# Temp_Hum_Sensor_Schematic_Rev1.net
KiCad netlist of a schematic drawn in EAGLE
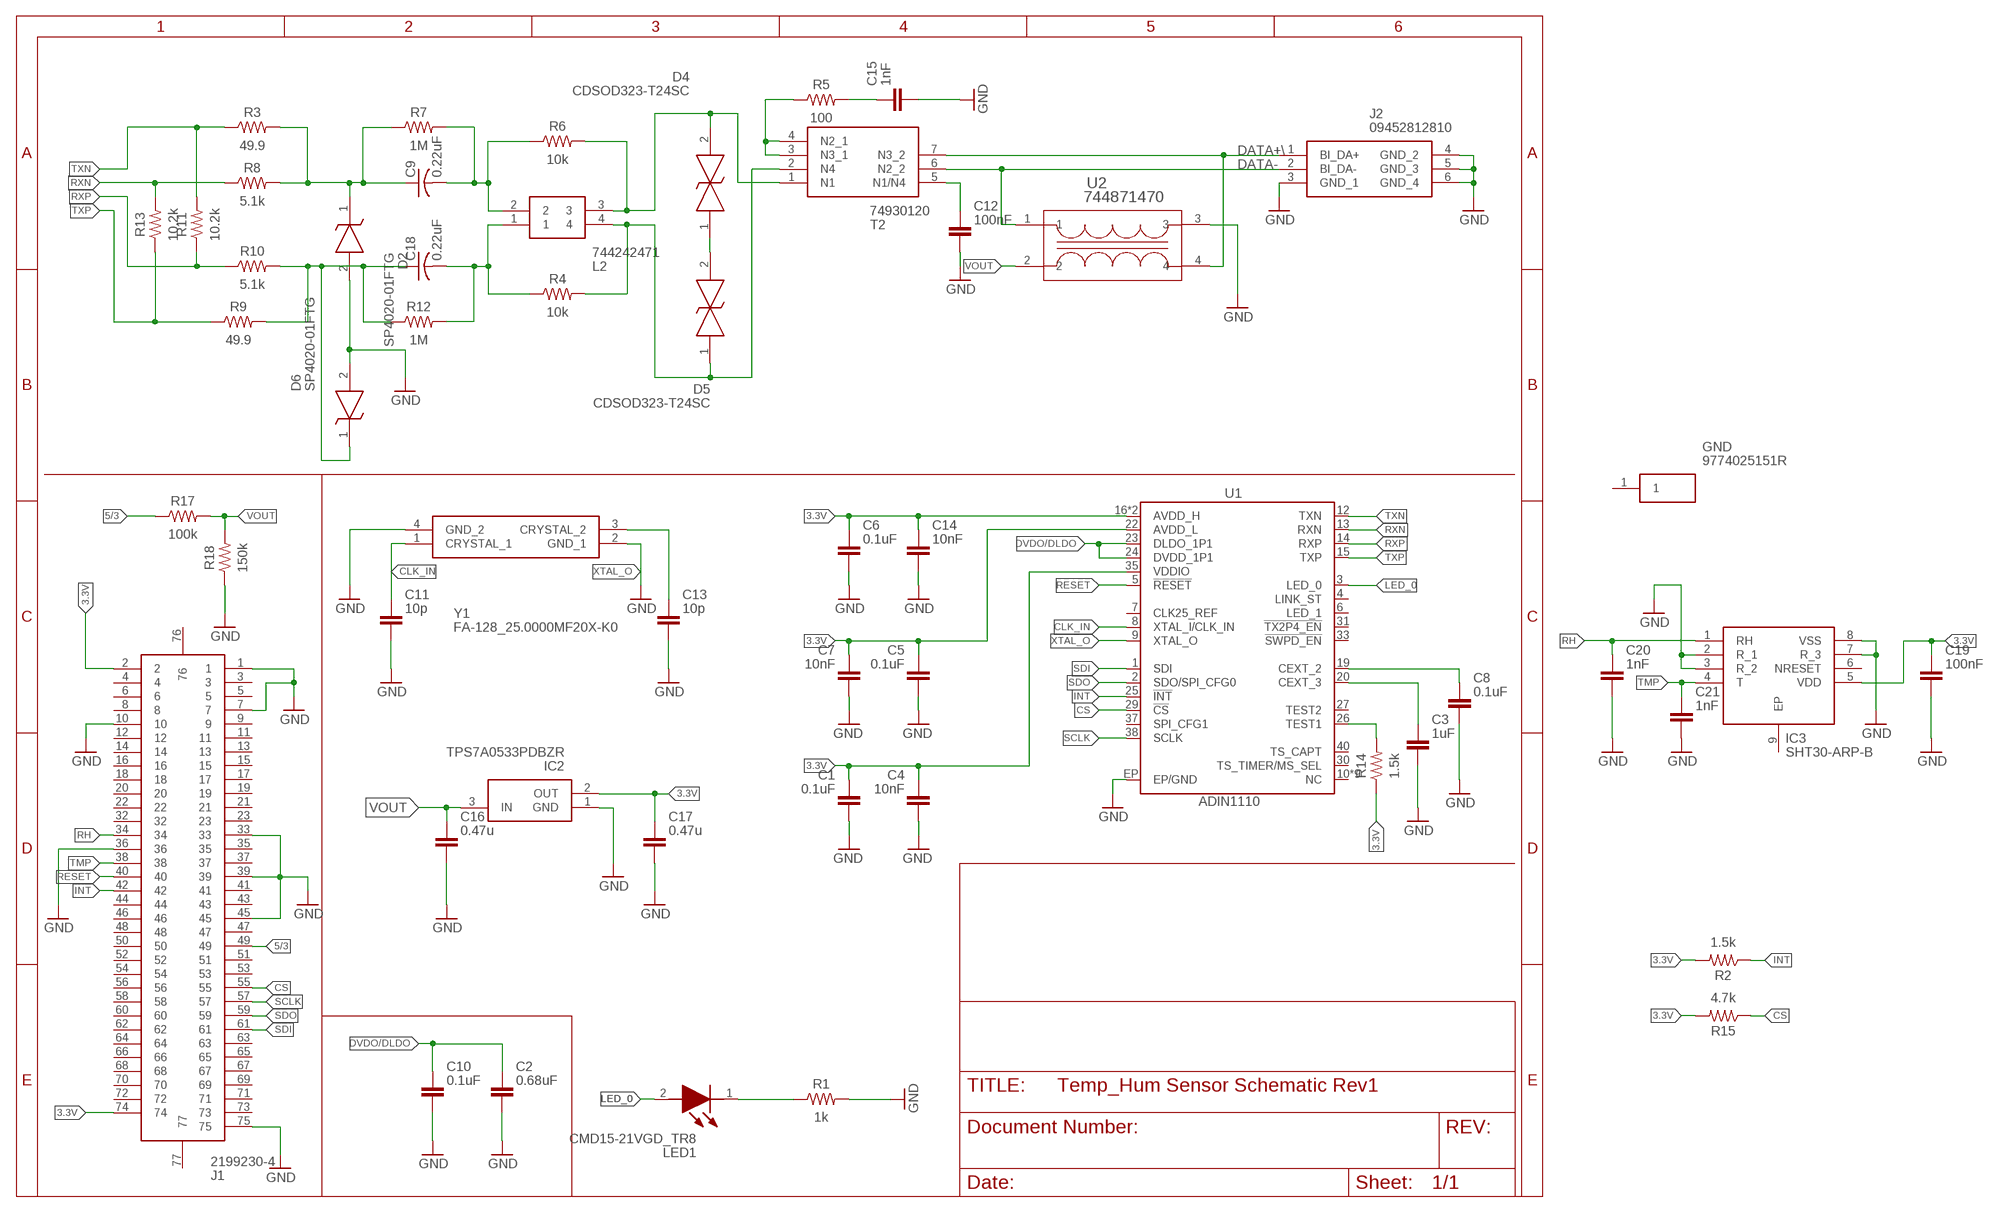
[diagram p0: schematic, sheet 1]

(export (version "E")
  (design (tool "Eeschema 10.0.6"))
  (components
    (comp (ref "C1")
      (value "0.1uF")
      (footprint "eagle-import:CAPC1005X60")
      (libsource (lib "eagle-import") (part "CCHIP-0402(1005-METRIC)_"))
    )
    (comp (ref "C2")
      (value "0.68uF")
      (footprint "eagle-import:CAPC1005X60")
      (libsource (lib "eagle-import") (part "CCHIP-0402(1005-METRIC)_"))
    )
    (comp (ref "C3")
      (value "1uF")
      (footprint "eagle-import:CAPC1005X60")
      (libsource (lib "eagle-import") (part "CCHIP-0402(1005-METRIC)_"))
    )
    (comp (ref "C4")
      (value "10nF")
      (footprint "eagle-import:CAPC1005X60")
      (libsource (lib "eagle-import") (part "CCHIP-0402(1005-METRIC)_"))
    )
    (comp (ref "C5")
      (value "0.1uF")
      (footprint "eagle-import:CAPC1005X60")
      (libsource (lib "eagle-import") (part "CCHIP-0402(1005-METRIC)_"))
    )
    (comp (ref "C6")
      (value "0.1uF")
      (footprint "eagle-import:CAPC1005X60")
      (libsource (lib "eagle-import") (part "CCHIP-0402(1005-METRIC)_"))
    )
    (comp (ref "C7")
      (value "10nF")
      (footprint "eagle-import:CAPC1005X60")
      (libsource (lib "eagle-import") (part "CCHIP-0402(1005-METRIC)_"))
    )
    (comp (ref "C8")
      (value "0.1uF")
      (footprint "eagle-import:CAPC1005X60")
      (libsource (lib "eagle-import") (part "CCHIP-0402(1005-METRIC)_"))
    )
    (comp (ref "C9")
      (value "0.22uF")
      (footprint "eagle-import:CAPC3216X135")
      (libsource (lib "eagle-import") (part "C-USCHIP-1206(3216-METRIC)_"))
    )
    (comp (ref "C10")
      (value "0.1uF")
      (footprint "eagle-import:CAPC1005X60")
      (libsource (lib "eagle-import") (part "CCHIP-0402(1005-METRIC)_"))
    )
    (comp (ref "C11")
      (value "10p")
      (footprint "eagle-import:CAPC1005X60")
      (libsource (lib "eagle-import") (part "CCHIP-0402(1005-METRIC)_"))
    )
    (comp (ref "C12")
      (value "100nF")
      (footprint "eagle-import:CAPC1005X60")
      (libsource (lib "eagle-import") (part "CCHIP-0402(1005-METRIC)_"))
    )
    (comp (ref "C13")
      (value "10p")
      (footprint "eagle-import:CAPC1005X60")
      (libsource (lib "eagle-import") (part "CCHIP-0402(1005-METRIC)_"))
    )
    (comp (ref "C14")
      (value "10nF")
      (footprint "eagle-import:CAPC1005X60")
      (libsource (lib "eagle-import") (part "CCHIP-0402(1005-METRIC)_"))
    )
    (comp (ref "C15")
      (value "1nF")
      (footprint "eagle-import:CAPC1005X60")
      (libsource (lib "eagle-import") (part "CCHIP-0402(1005-METRIC)_"))
    )
    (comp (ref "C16")
      (value "0.47u")
      (footprint "eagle-import:CAPC1005X60")
      (libsource (lib "eagle-import") (part "CCHIP-0402(1005-METRIC)_"))
    )
    (comp (ref "C17")
      (value "0.47u")
      (footprint "eagle-import:CAPC1005X60")
      (libsource (lib "eagle-import") (part "CCHIP-0402(1005-METRIC)_"))
    )
    (comp (ref "C18")
      (value "0.22uF")
      (footprint "eagle-import:CAPC3216X135")
      (libsource (lib "eagle-import") (part "C-USCHIP-1206(3216-METRIC)_"))
    )
    (comp (ref "C19")
      (value "100nF")
      (footprint "eagle-import:CAPC1005X60")
      (libsource (lib "eagle-import") (part "CCHIP-0402(1005-METRIC)_"))
    )
    (comp (ref "C20")
      (value "1nF")
      (footprint "eagle-import:CAPC1005X60")
      (libsource (lib "eagle-import") (part "CCHIP-0402(1005-METRIC)_"))
    )
    (comp (ref "C21")
      (value "1nF")
      (footprint "eagle-import:CAPC1005X60")
      (libsource (lib "eagle-import") (part "CCHIP-0402(1005-METRIC)_"))
    )
    (comp (ref "D2")
      (value "SP4020-01FTG")
      (footprint "eagle-import:SOD2613X114N")
      (fields (field (name "MOUSER_PART_NUMBER") "576-SP4020-01FTG"))
      (libsource (lib "eagle-import") (part "SP4020-01FTG"))
    )
    (comp (ref "D4")
      (value "CDSOD323-T24SC")
      (footprint "eagle-import:SOD2513X114N")
      (fields (field (name "MOUSER_PART_NUMBER") "652-CDSOD323-T24SC"))
      (libsource (lib "eagle-import") (part "CDSOD323-T24SC"))
    )
    (comp (ref "D5")
      (value "CDSOD323-T24SC")
      (footprint "eagle-import:SOD2513X114N")
      (fields (field (name "MOUSER_PART_NUMBER") "652-CDSOD323-T24SC"))
      (libsource (lib "eagle-import") (part "CDSOD323-T24SC"))
    )
    (comp (ref "D6")
      (value "SP4020-01FTG")
      (footprint "eagle-import:SOD2613X114N")
      (fields (field (name "MOUSER_PART_NUMBER") "576-SP4020-01FTG"))
      (libsource (lib "eagle-import") (part "SP4020-01FTG"))
    )
    (comp (ref "GND")
      (value "9774025151R")
      (footprint "eagle-import:9774025151R")
      (fields (field (name "MOUSER_PART_NUMBER") "710-9774025151R"))
      (libsource (lib "eagle-import") (part "9774025151R"))
    )
    (comp (ref "IC2")
      (value "TPS7A0533PDBZR")
      (footprint "eagle-import:SOT95P237X112-3N")
      (fields (field (name "MOUSER_PART_NUMBER") "595-TPS7A0533PDBZR"))
      (libsource (lib "eagle-import") (part "TPS7A0533PDBZR"))
    )
    (comp (ref "IC3")
      (value "SHT30-ARP-B")
      (footprint "eagle-import:SON50P250X250X100-9N")
      (fields (field (name "MOUSER_PART_NUMBER") "403-SHT30-ARP-B"))
      (libsource (lib "eagle-import") (part "SHT30-ARP-B"))
    )
    (comp (ref "J1")
      (value "2199230-4")
      (footprint "eagle-import:21992304")
      (fields (field (name "MOUSER_PART_NUMBER") "571-2199230-4"))
      (libsource (lib "eagle-import") (part "2199230-4"))
    )
    (comp (ref "J2")
      (value "09452812810")
      (footprint "eagle-import:09452812810")
      (fields (field (name "MOUSER_PART_NUMBER") "617-09452812810"))
      (libsource (lib "eagle-import") (part "09452812810"))
    )
    (comp (ref "L2")
      (value "744242471")
      (footprint "eagle-import:744242471")
      (fields (field (name "MOUSER_PART_NUMBER") "710-744242471"))
      (libsource (lib "eagle-import") (part "744242471"))
    )
    (comp (ref "LED1")
      (value "CMD15-21VGD_TR8")
      (footprint "eagle-import:LEDC3215X130N")
      (fields
        (field (name "ARROW_PART_NUMBER") "CMD15-21VGD/TR8")
        (field (name "MOUSER_PART_NUMBER") "606-CMD15-21VGD/TR8")
      )
      (libsource (lib "eagle-import") (part "CMD15-21VGD_TR8"))
    )
    (comp (ref "R1")
      (value "1k")
      (footprint "eagle-import:RESC1005X40")
      (libsource (lib "eagle-import") (part "R-USCHIP-0402(1005-METRIC)_"))
    )
    (comp (ref "R2")
      (value "1.5k")
      (footprint "eagle-import:RESC1005X40")
      (libsource (lib "eagle-import") (part "R-USCHIP-0402(1005-METRIC)_"))
    )
    (comp (ref "R3")
      (value "49.9")
      (footprint "eagle-import:RESC1005X40")
      (libsource (lib "eagle-import") (part "R-USCHIP-0402(1005-METRIC)_"))
    )
    (comp (ref "R4")
      (value "10k")
      (footprint "eagle-import:RESC1005X40")
      (libsource (lib "eagle-import") (part "R-USCHIP-0402(1005-METRIC)_"))
    )
    (comp (ref "R5")
      (value "100")
      (footprint "eagle-import:RESC1005X40")
      (libsource (lib "eagle-import") (part "R-USCHIP-0402(1005-METRIC)_"))
    )
    (comp (ref "R6")
      (value "10k")
      (footprint "eagle-import:RESC1005X40")
      (libsource (lib "eagle-import") (part "R-USCHIP-0402(1005-METRIC)_"))
    )
    (comp (ref "R7")
      (value "1M")
      (footprint "eagle-import:RESC1005X40")
      (libsource (lib "eagle-import") (part "R-USCHIP-0402(1005-METRIC)_"))
    )
    (comp (ref "R8")
      (value "5.1k")
      (footprint "eagle-import:RESC1005X40")
      (libsource (lib "eagle-import") (part "R-USCHIP-0402(1005-METRIC)_"))
    )
    (comp (ref "R9")
      (value "49.9")
      (footprint "eagle-import:RESC1005X40")
      (libsource (lib "eagle-import") (part "R-USCHIP-0402(1005-METRIC)_"))
    )
    (comp (ref "R10")
      (value "5.1k")
      (footprint "eagle-import:RESC1005X40")
      (libsource (lib "eagle-import") (part "R-USCHIP-0402(1005-METRIC)_"))
    )
    (comp (ref "R11")
      (value "10.2k")
      (footprint "eagle-import:RESC1005X40")
      (libsource (lib "eagle-import") (part "R-USCHIP-0402(1005-METRIC)_"))
    )
    (comp (ref "R12")
      (value "1M")
      (footprint "eagle-import:RESC1005X40")
      (libsource (lib "eagle-import") (part "R-USCHIP-0402(1005-METRIC)_"))
    )
    (comp (ref "R13")
      (value "10.2k")
      (footprint "eagle-import:RESC1005X40")
      (libsource (lib "eagle-import") (part "R-USCHIP-0402(1005-METRIC)_"))
    )
    (comp (ref "R14")
      (value "1.5k")
      (footprint "eagle-import:RESC1005X40")
      (libsource (lib "eagle-import") (part "R-USCHIP-0402(1005-METRIC)_"))
    )
    (comp (ref "R15")
      (value "4.7k")
      (footprint "eagle-import:RESC1005X40")
      (libsource (lib "eagle-import") (part "R-USCHIP-0402(1005-METRIC)_"))
    )
    (comp (ref "R17")
      (value "100k")
      (footprint "eagle-import:RESC1005X40")
      (libsource (lib "eagle-import") (part "R-USCHIP-0402(1005-METRIC)_"))
    )
    (comp (ref "R18")
      (value "150k")
      (footprint "eagle-import:RESC1005X40")
      (libsource (lib "eagle-import") (part "R-USCHIP-0402(1005-METRIC)_"))
    )
    (comp (ref "T2")
      (value "74930120")
      (footprint "eagle-import:74930120")
      (fields (field (name "MOUSER_PART_NUMBER") "710-74930120"))
      (libsource (lib "eagle-import") (part "74930120"))
    )
    (comp (ref "U1")
      (value "ADIN1110")
      (footprint "eagle-import:LFCSP-40")
      (libsource (lib "eagle-import") (part "ADIN1110"))
    )
    (comp (ref "U2")
      (value "744871470")
      (footprint "eagle-import:SMT_871470_WRE")
      (fields (field (name "COPYRIGHT") "Copyright (C) 2023 Ultra Librarian. All rights reserved."))
      (libsource (lib "eagle-import") (part "744871470"))
    )
    (comp (ref "Y1")
      (value "FA-128_25.0000MF20X-K0")
      (footprint "eagle-import:FA128250000MF20XK0")
      (fields
        (field (name "MANUFACTURER_PART_NUMBER") "FA-128 25.0000MF20X-K0")
        (field (name "MOUSER_PART_NUMBER") "732-FA-12825F20X-K0")
      )
      (libsource (lib "eagle-import") (part "FA-128_25.0000MF20X-K0"))
    )
  )
  (nets
    (net (code "1") (name "/DATA+\\") (class "Default")
      (node (ref "J2") (pin "1") (pinfunction "BI_DA+_1") (pintype "bidirectional"))
      (node (ref "T2") (pin "7") (pinfunction "N3_2_7") (pintype "bidirectional"))
      (node (ref "U2") (pin "4") (pinfunction "4_4") (pintype "passive"))
    )
    (net (code "2") (name "/DATA-") (class "Default")
      (node (ref "J2") (pin "2") (pinfunction "BI_DA-_2") (pintype "bidirectional"))
      (node (ref "T2") (pin "6") (pinfunction "N2_2_6") (pintype "bidirectional"))
      (node (ref "U2") (pin "1") (pinfunction "1_1") (pintype "passive"))
    )
    (net (code "3") (name "3.3V") (class "Default")
      (node (ref "C1") (pin "1") (pinfunction "1_1") (pintype "passive"))
      (node (ref "C14") (pin "1") (pinfunction "1_1") (pintype "passive"))
      (node (ref "C17") (pin "1") (pinfunction "1_1") (pintype "passive"))
      (node (ref "C19") (pin "1") (pinfunction "1_1") (pintype "passive"))
      (node (ref "C4") (pin "1") (pinfunction "1_1") (pintype "passive"))
      (node (ref "C5") (pin "1") (pinfunction "1_1") (pintype "passive"))
      (node (ref "C6") (pin "1") (pinfunction "1_1") (pintype "passive"))
      (node (ref "C7") (pin "1") (pinfunction "1_1") (pintype "passive"))
      (node (ref "IC2") (pin "2") (pinfunction "OUT_2") (pintype "output"))
      (node (ref "IC3") (pin "5") (pinfunction "VDD_5") (pintype "bidirectional"))
      (node (ref "J1") (pin "2") (pinfunction "2_2") (pintype "bidirectional"))
      (node (ref "J1") (pin "74") (pinfunction "74_74") (pintype "bidirectional"))
      (node (ref "R14") (pin "1") (pinfunction "1_1") (pintype "passive"))
      (node (ref "R15") (pin "2") (pinfunction "2_2") (pintype "passive"))
      (node (ref "R2") (pin "2") (pinfunction "2_2") (pintype "passive"))
      (node (ref "U1") (pin "16") (pinfunction "AVDD_H_16") (pintype "bidirectional"))
      (node (ref "U1") (pin "17") (pinfunction "AVDD_H_17") (pintype "bidirectional"))
      (node (ref "U1") (pin "22") (pinfunction "AVDD_L_22") (pintype "bidirectional"))
      (node (ref "U1") (pin "35") (pinfunction "VDDIO_35") (pintype "bidirectional"))
    )
    (net (code "4") (name "5{slash}3") (class "Default")
      (node (ref "J1") (pin "49") (pinfunction "49_49") (pintype "bidirectional"))
      (node (ref "R17") (pin "1") (pinfunction "1_1") (pintype "passive"))
    )
    (net (code "5") (name "CLK_IN") (class "Default")
      (node (ref "C11") (pin "1") (pinfunction "1_1") (pintype "passive"))
      (node (ref "U1") (pin "8") (pinfunction "XTAL_I/CLK_IN_8") (pintype "bidirectional"))
      (node (ref "Y1") (pin "1") (pinfunction "CRYSTAL_1_1") (pintype "bidirectional"))
    )
    (net (code "6") (name "CS") (class "Default")
      (node (ref "J1") (pin "55") (pinfunction "55_55") (pintype "bidirectional"))
      (node (ref "R15") (pin "1") (pinfunction "1_1") (pintype "passive"))
      (node (ref "U1") (pin "29") (pinfunction "~{CS}_29") (pintype "bidirectional"))
    )
    (net (code "7") (name "DVDO{slash}DLDO") (class "Default")
      (node (ref "C10") (pin "1") (pinfunction "1_1") (pintype "passive"))
      (node (ref "C2") (pin "1") (pinfunction "1_1") (pintype "passive"))
      (node (ref "U1") (pin "23") (pinfunction "DLDO_1P1_23") (pintype "bidirectional"))
      (node (ref "U1") (pin "24") (pinfunction "DVDD_1P1_24") (pintype "bidirectional"))
    )
    (net (code "8") (name "GND") (class "Default")
      (node (ref "C1") (pin "2") (pinfunction "2_2") (pintype "passive"))
      (node (ref "C10") (pin "2") (pinfunction "2_2") (pintype "passive"))
      (node (ref "C11") (pin "2") (pinfunction "2_2") (pintype "passive"))
      (node (ref "C12") (pin "2") (pinfunction "2_2") (pintype "passive"))
      (node (ref "C13") (pin "2") (pinfunction "2_2") (pintype "passive"))
      (node (ref "C14") (pin "2") (pinfunction "2_2") (pintype "passive"))
      (node (ref "C15") (pin "2") (pinfunction "2_2") (pintype "passive"))
      (node (ref "C16") (pin "2") (pinfunction "2_2") (pintype "passive"))
      (node (ref "C17") (pin "2") (pinfunction "2_2") (pintype "passive"))
      (node (ref "C19") (pin "2") (pinfunction "2_2") (pintype "passive"))
      (node (ref "C2") (pin "2") (pinfunction "2_2") (pintype "passive"))
      (node (ref "C20") (pin "2") (pinfunction "2_2") (pintype "passive"))
      (node (ref "C21") (pin "2") (pinfunction "2_2") (pintype "passive"))
      (node (ref "C3") (pin "2") (pinfunction "2_2") (pintype "passive"))
      (node (ref "C4") (pin "2") (pinfunction "2_2") (pintype "passive"))
      (node (ref "C5") (pin "2") (pinfunction "2_2") (pintype "passive"))
      (node (ref "C6") (pin "2") (pinfunction "2_2") (pintype "passive"))
      (node (ref "C7") (pin "2") (pinfunction "2_2") (pintype "passive"))
      (node (ref "C8") (pin "2") (pinfunction "2_2") (pintype "passive"))
      (node (ref "D2") (pin "2") (pinfunction "A_2") (pintype "bidirectional"))
      (node (ref "D6") (pin "2") (pinfunction "A_2") (pintype "bidirectional"))
      (node (ref "IC2") (pin "1") (pinfunction "GND_1") (pintype "power_in"))
      (node (ref "IC3") (pin "2") (pinfunction "R_1_2") (pintype "bidirectional"))
      (node (ref "IC3") (pin "3") (pinfunction "R_2_3") (pintype "bidirectional"))
      (node (ref "IC3") (pin "7") (pinfunction "R_3_7") (pintype "bidirectional"))
      (node (ref "IC3") (pin "8") (pinfunction "VSS_8") (pintype "bidirectional"))
      (node (ref "J1") (pin "1") (pinfunction "1_1") (pintype "bidirectional"))
      (node (ref "J1") (pin "10") (pinfunction "10_10") (pintype "bidirectional"))
      (node (ref "J1") (pin "33") (pinfunction "33_33") (pintype "bidirectional"))
      (node (ref "J1") (pin "36") (pinfunction "36_36") (pintype "bidirectional"))
      (node (ref "J1") (pin "39") (pinfunction "39_39") (pintype "bidirectional"))
      (node (ref "J1") (pin "45") (pinfunction "45_45") (pintype "bidirectional"))
      (node (ref "J1") (pin "7") (pinfunction "7_7") (pintype "bidirectional"))
      (node (ref "J1") (pin "75") (pinfunction "75_75") (pintype "bidirectional"))
      (node (ref "J2") (pin "3") (pinfunction "GND_1_3") (pintype "bidirectional"))
      (node (ref "J2") (pin "4") (pinfunction "GND_2_4") (pintype "bidirectional"))
      (node (ref "J2") (pin "5") (pinfunction "GND_3_5") (pintype "bidirectional"))
      (node (ref "J2") (pin "6") (pinfunction "GND_4_6") (pintype "bidirectional"))
      (node (ref "R1") (pin "2") (pinfunction "2_2") (pintype "passive"))
      (node (ref "R18") (pin "1") (pinfunction "1_1") (pintype "passive"))
      (node (ref "U1") (pin "EP") (pinfunction "EP/GND_EP") (pintype "bidirectional"))
      (node (ref "U2") (pin "3") (pinfunction "3_3") (pintype "passive"))
      (node (ref "Y1") (pin "2") (pinfunction "GND_1_2") (pintype "bidirectional"))
      (node (ref "Y1") (pin "4") (pinfunction "GND_2_4") (pintype "bidirectional"))
    )
    (net (code "9") (name "INT") (class "Default")
      (node (ref "J1") (pin "42") (pinfunction "42_42") (pintype "bidirectional"))
      (node (ref "R2") (pin "1") (pinfunction "1_1") (pintype "passive"))
      (node (ref "U1") (pin "25") (pinfunction "~{INT}_25") (pintype "bidirectional"))
    )
    (net (code "10") (name "LED_0") (class "Default")
      (node (ref "LED1") (pin "2") (pinfunction "A_2") (pintype "bidirectional"))
      (node (ref "U1") (pin "3") (pinfunction "LED_0_3") (pintype "bidirectional"))
    )
    (net (code "11") (name "Net-(C9-Pad2)") (class "Default")
      (node (ref "C9") (pin "2") (pinfunction "2_2") (pintype "passive"))
      (node (ref "L2") (pin "2") (pinfunction "2_2") (pintype "bidirectional"))
      (node (ref "R6") (pin "1") (pinfunction "1_1") (pintype "passive"))
      (node (ref "R7") (pin "2") (pinfunction "2_2") (pintype "passive"))
    )
    (net (code "12") (name "Net-(C15-Pad1)") (class "Default")
      (node (ref "C15") (pin "1") (pinfunction "1_1") (pintype "passive"))
      (node (ref "R5") (pin "2") (pinfunction "2_2") (pintype "passive"))
    )
    (net (code "13") (name "Net-(C18-Pad2)") (class "Default")
      (node (ref "C18") (pin "2") (pinfunction "2_2") (pintype "passive"))
      (node (ref "L2") (pin "1") (pinfunction "1_1") (pintype "bidirectional"))
      (node (ref "R12") (pin "2") (pinfunction "2_2") (pintype "passive"))
      (node (ref "R4") (pin "1") (pinfunction "1_1") (pintype "passive"))
    )
    (net (code "14") (name "Net-(D2-K)") (class "Default")
      (node (ref "C9") (pin "1") (pinfunction "1_1") (pintype "passive"))
      (node (ref "D2") (pin "1") (pinfunction "K_1") (pintype "bidirectional"))
      (node (ref "R3") (pin "2") (pinfunction "2_2") (pintype "passive"))
      (node (ref "R7") (pin "1") (pinfunction "1_1") (pintype "passive"))
      (node (ref "R8") (pin "2") (pinfunction "2_2") (pintype "passive"))
    )
    (net (code "15") (name "Net-(D4-Pad1)") (class "Default")
      (node (ref "D4") (pin "1") (pinfunction "1_1") (pintype "bidirectional"))
      (node (ref "D5") (pin "2") (pinfunction "2_2") (pintype "bidirectional"))
    )
    (net (code "16") (name "Net-(D6-K)") (class "Default")
      (node (ref "C18") (pin "1") (pinfunction "1_1") (pintype "passive"))
      (node (ref "D6") (pin "1") (pinfunction "K_1") (pintype "bidirectional"))
      (node (ref "R10") (pin "2") (pinfunction "2_2") (pintype "passive"))
      (node (ref "R12") (pin "1") (pinfunction "1_1") (pintype "passive"))
      (node (ref "R9") (pin "2") (pinfunction "2_2") (pintype "passive"))
    )
    (net (code "17") (name "Net-(LED1-K)") (class "Default")
      (node (ref "LED1") (pin "1") (pinfunction "K_1") (pintype "bidirectional"))
      (node (ref "R1") (pin "1") (pinfunction "1_1") (pintype "passive"))
    )
    (net (code "18") (name "Net-(T2-N1)") (class "Default")
      (node (ref "D4") (pin "2") (pinfunction "2_2") (pintype "bidirectional"))
      (node (ref "L2") (pin "3") (pinfunction "3_3") (pintype "bidirectional"))
      (node (ref "R6") (pin "2") (pinfunction "2_2") (pintype "passive"))
      (node (ref "T2") (pin "1") (pinfunction "N1_1") (pintype "bidirectional"))
    )
    (net (code "19") (name "Net-(T2-N1{slash}N4)") (class "Default")
      (node (ref "C12") (pin "1") (pinfunction "1_1") (pintype "passive"))
      (node (ref "T2") (pin "5") (pinfunction "N1/N4_5") (pintype "bidirectional"))
    )
    (net (code "20") (name "Net-(T2-N2_1)") (class "Default")
      (node (ref "R5") (pin "1") (pinfunction "1_1") (pintype "passive"))
      (node (ref "T2") (pin "3") (pinfunction "N3_1_3") (pintype "bidirectional"))
      (node (ref "T2") (pin "4") (pinfunction "N2_1_4") (pintype "bidirectional"))
    )
    (net (code "21") (name "Net-(T2-N4)") (class "Default")
      (node (ref "D5") (pin "1") (pinfunction "1_1") (pintype "bidirectional"))
      (node (ref "L2") (pin "4") (pinfunction "4_4") (pintype "bidirectional"))
      (node (ref "R4") (pin "2") (pinfunction "2_2") (pintype "passive"))
      (node (ref "T2") (pin "2") (pinfunction "N4_2") (pintype "bidirectional"))
    )
    (net (code "22") (name "Net-(U1-CEXT_2)") (class "Default")
      (node (ref "C8") (pin "1") (pinfunction "1_1") (pintype "passive"))
      (node (ref "U1") (pin "19") (pinfunction "CEXT_2_19") (pintype "bidirectional"))
    )
    (net (code "23") (name "Net-(U1-CEXT_3)") (class "Default")
      (node (ref "C3") (pin "1") (pinfunction "1_1") (pintype "passive"))
      (node (ref "U1") (pin "20") (pinfunction "CEXT_3_20") (pintype "bidirectional"))
    )
    (net (code "24") (name "Net-(U1-TEST1)") (class "Default")
      (node (ref "R14") (pin "2") (pinfunction "2_2") (pintype "passive"))
      (node (ref "U1") (pin "26") (pinfunction "TEST1_26") (pintype "bidirectional"))
    )
    (net (code "25") (name "RESET") (class "Default")
      (node (ref "J1") (pin "40") (pinfunction "40_40") (pintype "bidirectional"))
      (node (ref "U1") (pin "5") (pinfunction "~{RESET}_5") (pintype "bidirectional"))
    )
    (net (code "26") (name "RH") (class "Default")
      (node (ref "C20") (pin "1") (pinfunction "1_1") (pintype "passive"))
      (node (ref "IC3") (pin "1") (pinfunction "RH_1") (pintype "bidirectional"))
      (node (ref "J1") (pin "34") (pinfunction "34_34") (pintype "bidirectional"))
    )
    (net (code "27") (name "RXN") (class "Default")
      (node (ref "R13") (pin "2") (pinfunction "2_2") (pintype "passive"))
      (node (ref "R8") (pin "1") (pinfunction "1_1") (pintype "passive"))
      (node (ref "U1") (pin "13") (pinfunction "RXN_13") (pintype "bidirectional"))
    )
    (net (code "28") (name "RXP") (class "Default")
      (node (ref "R10") (pin "1") (pinfunction "1_1") (pintype "passive"))
      (node (ref "R11") (pin "1") (pinfunction "1_1") (pintype "passive"))
      (node (ref "U1") (pin "14") (pinfunction "RXP_14") (pintype "bidirectional"))
    )
    (net (code "29") (name "SCLK") (class "Default")
      (node (ref "J1") (pin "57") (pinfunction "57_57") (pintype "bidirectional"))
      (node (ref "U1") (pin "38") (pinfunction "SCLK_38") (pintype "bidirectional"))
    )
    (net (code "30") (name "SDI") (class "Default")
      (node (ref "J1") (pin "61") (pinfunction "61_61") (pintype "bidirectional"))
      (node (ref "U1") (pin "1") (pinfunction "SDI_1") (pintype "bidirectional"))
    )
    (net (code "31") (name "SDO") (class "Default")
      (node (ref "J1") (pin "59") (pinfunction "59_59") (pintype "bidirectional"))
      (node (ref "U1") (pin "2") (pinfunction "SDO/SPI_CFG0_2") (pintype "bidirectional"))
    )
    (net (code "32") (name "TMP") (class "Default")
      (node (ref "C21") (pin "1") (pinfunction "1_1") (pintype "passive"))
      (node (ref "IC3") (pin "4") (pinfunction "T_4") (pintype "bidirectional"))
      (node (ref "J1") (pin "38") (pinfunction "38_38") (pintype "bidirectional"))
    )
    (net (code "33") (name "TXN") (class "Default")
      (node (ref "R11") (pin "2") (pinfunction "2_2") (pintype "passive"))
      (node (ref "R3") (pin "1") (pinfunction "1_1") (pintype "passive"))
      (node (ref "U1") (pin "12") (pinfunction "TXN_12") (pintype "bidirectional"))
    )
    (net (code "34") (name "TXP") (class "Default")
      (node (ref "R13") (pin "1") (pinfunction "1_1") (pintype "passive"))
      (node (ref "R9") (pin "1") (pinfunction "1_1") (pintype "passive"))
      (node (ref "U1") (pin "15") (pinfunction "TXP_15") (pintype "bidirectional"))
    )
    (net (code "35") (name "VOUT") (class "Default")
      (node (ref "C16") (pin "1") (pinfunction "1_1") (pintype "passive"))
      (node (ref "IC2") (pin "3") (pinfunction "IN_3") (pintype "input"))
      (node (ref "R17") (pin "2") (pinfunction "2_2") (pintype "passive"))
      (node (ref "R18") (pin "2") (pinfunction "2_2") (pintype "passive"))
      (node (ref "U2") (pin "2") (pinfunction "2_2") (pintype "passive"))
    )
    (net (code "36") (name "XTAL_O") (class "Default")
      (node (ref "C13") (pin "1") (pinfunction "1_1") (pintype "passive"))
      (node (ref "U1") (pin "9") (pinfunction "XTAL_O_9") (pintype "bidirectional"))
      (node (ref "Y1") (pin "3") (pinfunction "CRYSTAL_2_3") (pintype "bidirectional"))
    )
    (net (code "37") (name "unconnected-(GND-Pad1)") (class "Default")
      (node (ref "GND") (pin "1") (pinfunction "1_1") (pintype "bidirectional"))
    )
    (net (code "38") (name "unconnected-(IC3-EP-Pad9)") (class "Default")
      (node (ref "IC3") (pin "9") (pinfunction "EP_9") (pintype "bidirectional"))
    )
    (net (code "39") (name "unconnected-(IC3-NRESET-Pad6)") (class "Default")
      (node (ref "IC3") (pin "6") (pinfunction "NRESET_6") (pintype "bidirectional"))
    )
    (net (code "40") (name "unconnected-(J1-Pad3)") (class "Default")
      (node (ref "J1") (pin "3") (pinfunction "3_3") (pintype "bidirectional"))
    )
    (net (code "41") (name "unconnected-(J1-Pad4)") (class "Default")
      (node (ref "J1") (pin "4") (pinfunction "4_4") (pintype "bidirectional"))
    )
    (net (code "42") (name "unconnected-(J1-Pad5)") (class "Default")
      (node (ref "J1") (pin "5") (pinfunction "5_5") (pintype "bidirectional"))
    )
    (net (code "43") (name "unconnected-(J1-Pad6)") (class "Default")
      (node (ref "J1") (pin "6") (pinfunction "6_6") (pintype "bidirectional"))
    )
    (net (code "44") (name "unconnected-(J1-Pad8)") (class "Default")
      (node (ref "J1") (pin "8") (pinfunction "8_8") (pintype "bidirectional"))
    )
    (net (code "45") (name "unconnected-(J1-Pad9)") (class "Default")
      (node (ref "J1") (pin "9") (pinfunction "9_9") (pintype "bidirectional"))
    )
    (net (code "46") (name "unconnected-(J1-Pad11)") (class "Default")
      (node (ref "J1") (pin "11") (pinfunction "11_11") (pintype "bidirectional"))
    )
    (net (code "47") (name "unconnected-(J1-Pad12)") (class "Default")
      (node (ref "J1") (pin "12") (pinfunction "12_12") (pintype "bidirectional"))
    )
    (net (code "48") (name "unconnected-(J1-Pad13)") (class "Default")
      (node (ref "J1") (pin "13") (pinfunction "13_13") (pintype "bidirectional"))
    )
    (net (code "49") (name "unconnected-(J1-Pad14)") (class "Default")
      (node (ref "J1") (pin "14") (pinfunction "14_14") (pintype "bidirectional"))
    )
    (net (code "50") (name "unconnected-(J1-Pad15)") (class "Default")
      (node (ref "J1") (pin "15") (pinfunction "15_15") (pintype "bidirectional"))
    )
    (net (code "51") (name "unconnected-(J1-Pad16)") (class "Default")
      (node (ref "J1") (pin "16") (pinfunction "16_16") (pintype "bidirectional"))
    )
    (net (code "52") (name "unconnected-(J1-Pad17)") (class "Default")
      (node (ref "J1") (pin "17") (pinfunction "17_17") (pintype "bidirectional"))
    )
    (net (code "53") (name "unconnected-(J1-Pad18)") (class "Default")
      (node (ref "J1") (pin "18") (pinfunction "18_18") (pintype "bidirectional"))
    )
    (net (code "54") (name "unconnected-(J1-Pad19)") (class "Default")
      (node (ref "J1") (pin "19") (pinfunction "19_19") (pintype "bidirectional"))
    )
    (net (code "55") (name "unconnected-(J1-Pad20)") (class "Default")
      (node (ref "J1") (pin "20") (pinfunction "20_20") (pintype "bidirectional"))
    )
    (net (code "56") (name "unconnected-(J1-Pad21)") (class "Default")
      (node (ref "J1") (pin "21") (pinfunction "21_21") (pintype "bidirectional"))
    )
    (net (code "57") (name "unconnected-(J1-Pad22)") (class "Default")
      (node (ref "J1") (pin "22") (pinfunction "22_22") (pintype "bidirectional"))
    )
    (net (code "58") (name "unconnected-(J1-Pad23)") (class "Default")
      (node (ref "J1") (pin "23") (pinfunction "23_23") (pintype "bidirectional"))
    )
    (net (code "59") (name "unconnected-(J1-Pad32)") (class "Default")
      (node (ref "J1") (pin "32") (pinfunction "32_32") (pintype "bidirectional"))
    )
    (net (code "60") (name "unconnected-(J1-Pad35)") (class "Default")
      (node (ref "J1") (pin "35") (pinfunction "35_35") (pintype "bidirectional"))
    )
    (net (code "61") (name "unconnected-(J1-Pad37)") (class "Default")
      (node (ref "J1") (pin "37") (pinfunction "37_37") (pintype "bidirectional"))
    )
    (net (code "62") (name "unconnected-(J1-Pad41)") (class "Default")
      (node (ref "J1") (pin "41") (pinfunction "41_41") (pintype "bidirectional"))
    )
    (net (code "63") (name "unconnected-(J1-Pad43)") (class "Default")
      (node (ref "J1") (pin "43") (pinfunction "43_43") (pintype "bidirectional"))
    )
    (net (code "64") (name "unconnected-(J1-Pad44)") (class "Default")
      (node (ref "J1") (pin "44") (pinfunction "44_44") (pintype "bidirectional"))
    )
    (net (code "65") (name "unconnected-(J1-Pad46)") (class "Default")
      (node (ref "J1") (pin "46") (pinfunction "46_46") (pintype "bidirectional"))
    )
    (net (code "66") (name "unconnected-(J1-Pad47)") (class "Default")
      (node (ref "J1") (pin "47") (pinfunction "47_47") (pintype "bidirectional"))
    )
    (net (code "67") (name "unconnected-(J1-Pad48)") (class "Default")
      (node (ref "J1") (pin "48") (pinfunction "48_48") (pintype "bidirectional"))
    )
    (net (code "68") (name "unconnected-(J1-Pad50)") (class "Default")
      (node (ref "J1") (pin "50") (pinfunction "50_50") (pintype "bidirectional"))
    )
    (net (code "69") (name "unconnected-(J1-Pad51)") (class "Default")
      (node (ref "J1") (pin "51") (pinfunction "51_51") (pintype "bidirectional"))
    )
    (net (code "70") (name "unconnected-(J1-Pad52)") (class "Default")
      (node (ref "J1") (pin "52") (pinfunction "52_52") (pintype "bidirectional"))
    )
    (net (code "71") (name "unconnected-(J1-Pad53)") (class "Default")
      (node (ref "J1") (pin "53") (pinfunction "53_53") (pintype "bidirectional"))
    )
    (net (code "72") (name "unconnected-(J1-Pad54)") (class "Default")
      (node (ref "J1") (pin "54") (pinfunction "54_54") (pintype "bidirectional"))
    )
    (net (code "73") (name "unconnected-(J1-Pad56)") (class "Default")
      (node (ref "J1") (pin "56") (pinfunction "56_56") (pintype "bidirectional"))
    )
    (net (code "74") (name "unconnected-(J1-Pad58)") (class "Default")
      (node (ref "J1") (pin "58") (pinfunction "58_58") (pintype "bidirectional"))
    )
    (net (code "75") (name "unconnected-(J1-Pad60)") (class "Default")
      (node (ref "J1") (pin "60") (pinfunction "60_60") (pintype "bidirectional"))
    )
    (net (code "76") (name "unconnected-(J1-Pad62)") (class "Default")
      (node (ref "J1") (pin "62") (pinfunction "62_62") (pintype "bidirectional"))
    )
    (net (code "77") (name "unconnected-(J1-Pad63)") (class "Default")
      (node (ref "J1") (pin "63") (pinfunction "63_63") (pintype "bidirectional"))
    )
    (net (code "78") (name "unconnected-(J1-Pad64)") (class "Default")
      (node (ref "J1") (pin "64") (pinfunction "64_64") (pintype "bidirectional"))
    )
    (net (code "79") (name "unconnected-(J1-Pad65)") (class "Default")
      (node (ref "J1") (pin "65") (pinfunction "65_65") (pintype "bidirectional"))
    )
    (net (code "80") (name "unconnected-(J1-Pad66)") (class "Default")
      (node (ref "J1") (pin "66") (pinfunction "66_66") (pintype "bidirectional"))
    )
    (net (code "81") (name "unconnected-(J1-Pad67)") (class "Default")
      (node (ref "J1") (pin "67") (pinfunction "67_67") (pintype "bidirectional"))
    )
    (net (code "82") (name "unconnected-(J1-Pad68)") (class "Default")
      (node (ref "J1") (pin "68") (pinfunction "68_68") (pintype "bidirectional"))
    )
    (net (code "83") (name "unconnected-(J1-Pad69)") (class "Default")
      (node (ref "J1") (pin "69") (pinfunction "69_69") (pintype "bidirectional"))
    )
    (net (code "84") (name "unconnected-(J1-Pad70)") (class "Default")
      (node (ref "J1") (pin "70") (pinfunction "70_70") (pintype "bidirectional"))
    )
    (net (code "85") (name "unconnected-(J1-Pad71)") (class "Default")
      (node (ref "J1") (pin "71") (pinfunction "71_71") (pintype "bidirectional"))
    )
    (net (code "86") (name "unconnected-(J1-Pad72)") (class "Default")
      (node (ref "J1") (pin "72") (pinfunction "72_72") (pintype "bidirectional"))
    )
    (net (code "87") (name "unconnected-(J1-Pad73)") (class "Default")
      (node (ref "J1") (pin "73") (pinfunction "73_73") (pintype "bidirectional"))
    )
    (net (code "88") (name "unconnected-(J1-Pad76)") (class "Default")
      (node (ref "J1") (pin "76") (pinfunction "76_76") (pintype "bidirectional"))
    )
    (net (code "89") (name "unconnected-(J1-Pad77)") (class "Default")
      (node (ref "J1") (pin "77") (pinfunction "77_77") (pintype "bidirectional"))
    )
    (net (code "90") (name "unconnected-(U1-CLK25_REF-Pad7)") (class "Default")
      (node (ref "U1") (pin "7") (pinfunction "CLK25_REF_7") (pintype "bidirectional"))
    )
    (net (code "91") (name "unconnected-(U1-LED_1-Pad6)") (class "Default")
      (node (ref "U1") (pin "6") (pinfunction "LED_1_6") (pintype "bidirectional"))
    )
    (net (code "92") (name "unconnected-(U1-LINK_ST-Pad4)") (class "Default")
      (node (ref "U1") (pin "4") (pinfunction "LINK_ST_4") (pintype "bidirectional"))
    )
    (net (code "93") (name "unconnected-(U1-NC-Pad10)") (class "Default")
      (node (ref "U1") (pin "10") (pinfunction "NC_10") (pintype "no_connect"))
    )
    (net (code "94") (name "unconnected-(U1-NC-Pad11)") (class "Default")
      (node (ref "U1") (pin "11") (pinfunction "NC_11") (pintype "no_connect"))
    )
    (net (code "95") (name "unconnected-(U1-NC-Pad18)") (class "Default")
      (node (ref "U1") (pin "18") (pinfunction "NC_18") (pintype "no_connect"))
    )
    (net (code "96") (name "unconnected-(U1-NC-Pad21)") (class "Default")
      (node (ref "U1") (pin "21") (pinfunction "NC_21") (pintype "no_connect"))
    )
    (net (code "97") (name "unconnected-(U1-NC-Pad28)") (class "Default")
      (node (ref "U1") (pin "28") (pinfunction "NC_28") (pintype "no_connect"))
    )
    (net (code "98") (name "unconnected-(U1-NC-Pad32)") (class "Default")
      (node (ref "U1") (pin "32") (pinfunction "NC_32") (pintype "no_connect"))
    )
    (net (code "99") (name "unconnected-(U1-NC-Pad34)") (class "Default")
      (node (ref "U1") (pin "34") (pinfunction "NC_34") (pintype "no_connect"))
    )
    (net (code "100") (name "unconnected-(U1-NC-Pad36)") (class "Default")
      (node (ref "U1") (pin "36") (pinfunction "NC_36") (pintype "no_connect"))
    )
    (net (code "101") (name "unconnected-(U1-NC-Pad39)") (class "Default")
      (node (ref "U1") (pin "39") (pinfunction "NC_39") (pintype "no_connect"))
    )
    (net (code "102") (name "unconnected-(U1-SPI_CFG1-Pad37)") (class "Default")
      (node (ref "U1") (pin "37") (pinfunction "SPI_CFG1_37") (pintype "bidirectional"))
    )
    (net (code "103") (name "unconnected-(U1-TEST2-Pad27)") (class "Default")
      (node (ref "U1") (pin "27") (pinfunction "TEST2_27") (pintype "bidirectional"))
    )
    (net (code "104") (name "unconnected-(U1-TS_CAPT-Pad40)") (class "Default")
      (node (ref "U1") (pin "40") (pinfunction "TS_CAPT_40") (pintype "bidirectional"))
    )
    (net (code "105") (name "unconnected-(U1-TS_TIMER{slash}MS_SEL-Pad30)") (class "Default")
      (node (ref "U1") (pin "30") (pinfunction "TS_TIMER/MS_SEL_30") (pintype "bidirectional"))
    )
    (net (code "106") (name "unconnected-(U1-~{SWPD_EN}-Pad33)") (class "Default")
      (node (ref "U1") (pin "33") (pinfunction "~{SWPD_EN}_33") (pintype "bidirectional"))
    )
    (net (code "107") (name "unconnected-(U1-~{TX2P4_EN}-Pad31)") (class "Default")
      (node (ref "U1") (pin "31") (pinfunction "~{TX2P4_EN}_31") (pintype "bidirectional"))
    )
  )
)
